# SensorBoard.net
KiCad netlist of a schematic drawn in Altium Designer
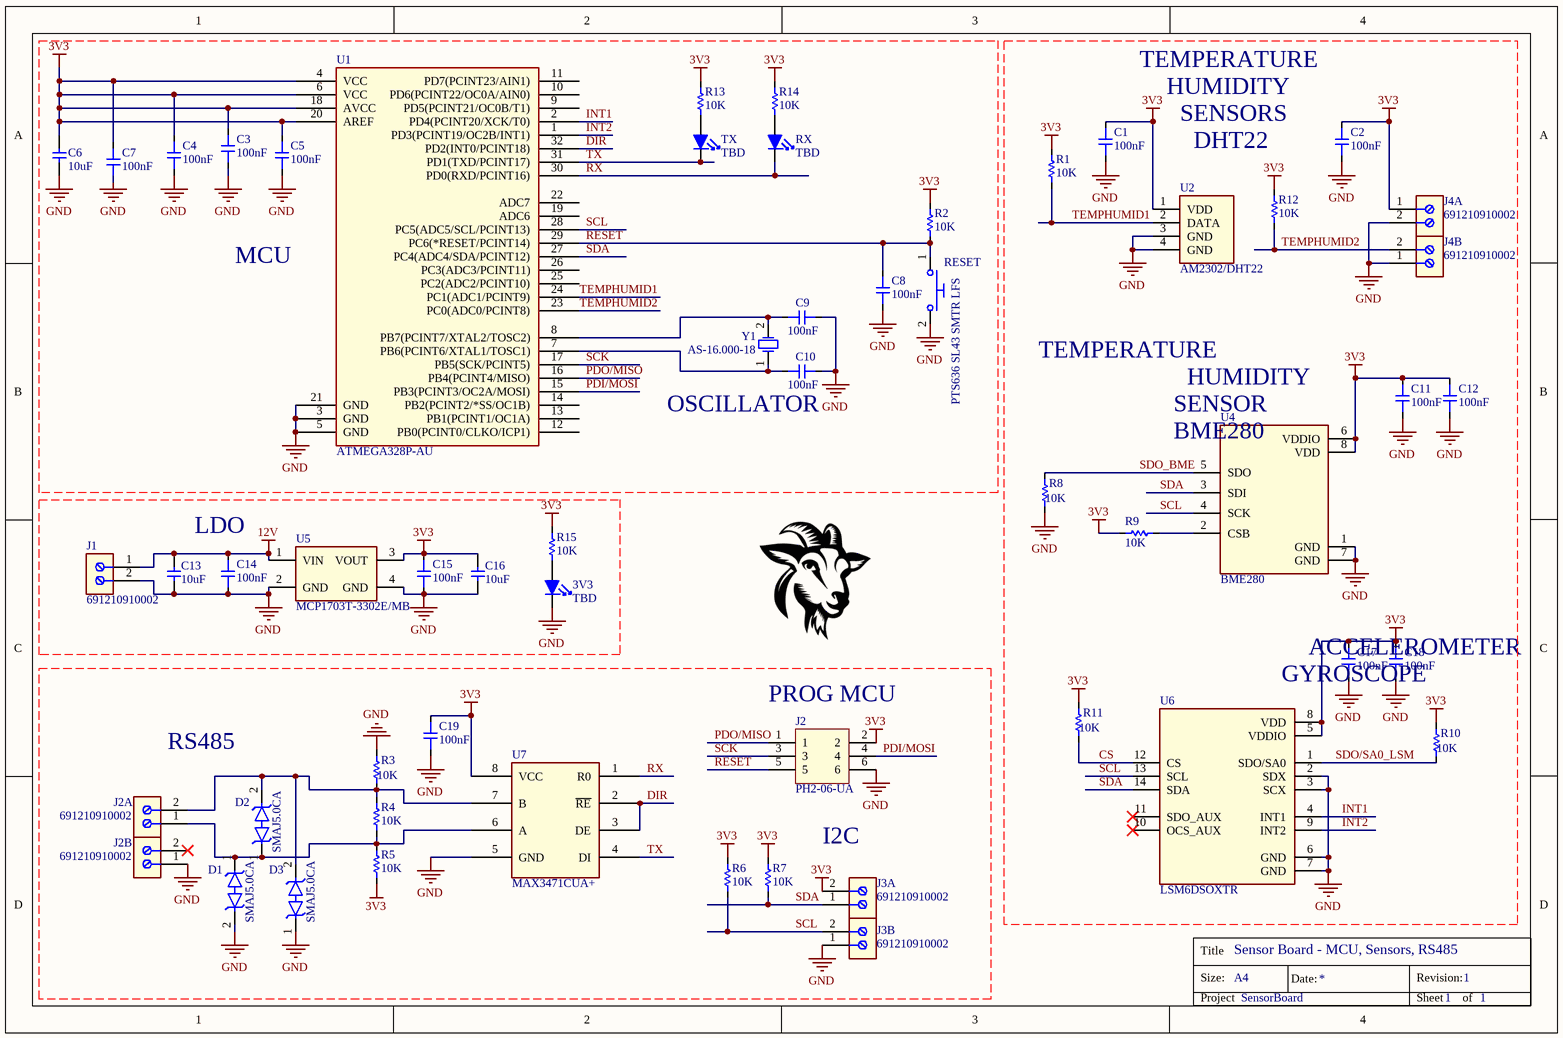
[diagram p0: SensorBoard.SchDoc]

(export (version "E")
  (design (tool "Eeschema 10.0.6"))
  (components
    (comp (ref "3V3")
      (value "TBD")
      (footprint "CASE0603")
      (description "Typical INFRARED GaAs LED")
      (libsource (lib "SensorBoard") (part "LED"))
    )
    (comp (ref "C1")
      (value "100nF")
      (footprint "CASE0603")
      (description "CAP CER 100nF 5% 25V X7R 0603")
      (fields (field (name "MFR") "KEMET"))
      (libsource (lib "SensorBoard") (part "Capacitor_100nF"))
    )
    (comp (ref "C2")
      (value "100nF")
      (footprint "CASE0603")
      (description "CAP CER 100nF 5% 25V X7R 0603")
      (fields (field (name "MFR") "KEMET"))
      (libsource (lib "SensorBoard") (part "Capacitor_100nF"))
    )
    (comp (ref "C3")
      (value "100nF")
      (footprint "CASE0603")
      (description "CAP CER 100nF 5% 25V X7R 0603")
      (fields (field (name "MFR") "KEMET"))
      (libsource (lib "SensorBoard") (part "Capacitor_100nF"))
    )
    (comp (ref "C4")
      (value "100nF")
      (footprint "CASE0603")
      (description "CAP CER 100nF 5% 25V X7R 0603")
      (fields (field (name "MFR") "KEMET"))
      (libsource (lib "SensorBoard") (part "Capacitor_100nF"))
    )
    (comp (ref "C5")
      (value "100nF")
      (footprint "CASE0603")
      (description "CAP CER 100nF 5% 25V X7R 0603")
      (fields (field (name "MFR") "KEMET"))
      (libsource (lib "SensorBoard") (part "Capacitor_100nF"))
    )
    (comp (ref "C6")
      (value "10uF")
      (footprint "CASE0603")
      (description "CAP CER 10uF 20% 25V X5R 0603")
      (fields (field (name "MFR") "TDK"))
      (libsource (lib "SensorBoard") (part "Capacitor_10uF"))
    )
    (comp (ref "C7")
      (value "100nF")
      (footprint "CASE0603")
      (description "CAP CER 100nF 5% 25V X7R 0603")
      (fields (field (name "MFR") "KEMET"))
      (libsource (lib "SensorBoard") (part "Capacitor_100nF"))
    )
    (comp (ref "C8")
      (value "100nF")
      (footprint "CASE0603")
      (description "CAP CER 100nF 5% 25V X7R 0603")
      (fields (field (name "MFR") "KEMET"))
      (libsource (lib "SensorBoard") (part "Capacitor_100nF"))
    )
    (comp (ref "C9")
      (value "100nF")
      (footprint "CASE0603")
      (description "CAP CER 100nF 5% 25V X7R 0603")
      (fields (field (name "MFR") "KEMET"))
      (libsource (lib "SensorBoard") (part "Capacitor_100nF"))
    )
    (comp (ref "C10")
      (value "100nF")
      (footprint "CASE0603")
      (description "CAP CER 100nF 5% 25V X7R 0603")
      (fields (field (name "MFR") "KEMET"))
      (libsource (lib "SensorBoard") (part "Capacitor_100nF"))
    )
    (comp (ref "C11")
      (value "100nF")
      (footprint "CASE0603")
      (description "CAP CER 100nF 5% 25V X7R 0603")
      (fields (field (name "MFR") "KEMET"))
      (libsource (lib "SensorBoard") (part "Capacitor_100nF"))
    )
    (comp (ref "C12")
      (value "100nF")
      (footprint "CASE0603")
      (description "CAP CER 100nF 5% 25V X7R 0603")
      (fields (field (name "MFR") "KEMET"))
      (libsource (lib "SensorBoard") (part "Capacitor_100nF"))
    )
    (comp (ref "C13")
      (value "10uF")
      (footprint "CASE0603")
      (description "CAP CER 10uF 20% 25V X5R 0603")
      (fields (field (name "MFR") "TDK"))
      (libsource (lib "SensorBoard") (part "Capacitor_10uF"))
    )
    (comp (ref "C14")
      (value "100nF")
      (footprint "CASE0603")
      (description "CAP CER 100nF 5% 25V X7R 0603")
      (fields (field (name "MFR") "KEMET"))
      (libsource (lib "SensorBoard") (part "Capacitor_100nF"))
    )
    (comp (ref "C15")
      (value "100nF")
      (footprint "CASE0603")
      (description "CAP CER 100nF 5% 25V X7R 0603")
      (fields (field (name "MFR") "KEMET"))
      (libsource (lib "SensorBoard") (part "Capacitor_100nF"))
    )
    (comp (ref "C16")
      (value "10uF")
      (footprint "CASE0603")
      (description "CAP CER 10uF 20% 25V X5R 0603")
      (fields (field (name "MFR") "TDK"))
      (libsource (lib "SensorBoard") (part "Capacitor_10uF"))
    )
    (comp (ref "C17")
      (value "100nF")
      (footprint "CASE0603")
      (description "CAP CER 100nF 5% 25V X7R 0603")
      (fields (field (name "MFR") "KEMET"))
      (libsource (lib "SensorBoard") (part "Capacitor_100nF"))
    )
    (comp (ref "C18")
      (value "100nF")
      (footprint "CASE0603")
      (description "CAP CER 100nF 5% 25V X7R 0603")
      (fields (field (name "MFR") "KEMET"))
      (libsource (lib "SensorBoard") (part "Capacitor_100nF"))
    )
    (comp (ref "C19")
      (value "100nF")
      (footprint "CASE0603")
      (description "CAP CER 100nF 5% 25V X7R 0603")
      (fields (field (name "MFR") "KEMET"))
      (libsource (lib "SensorBoard") (part "Capacitor_100nF"))
    )
    (comp (ref "D1")
      (value "SMAJ5.0CA")
      (footprint "SMA")
      (description "9.2V Clamp 43.5A Ipp Tvs Diode Surface Mount DO-214AC (SMA)")
      (fields (field (name "MFR") "Good-Ark Semiconductor"))
      (libsource (lib "SensorBoard") (part "Diode_SMAJ5.0CA"))
    )
    (comp (ref "D2")
      (value "SMAJ5.0CA")
      (footprint "SMA")
      (description "9.2V Clamp 43.5A Ipp Tvs Diode Surface Mount DO-214AC (SMA)")
      (fields (field (name "MFR") "Good-Ark Semiconductor"))
      (libsource (lib "SensorBoard") (part "Diode_SMAJ5.0CA"))
    )
    (comp (ref "D3")
      (value "SMAJ5.0CA")
      (footprint "SMA")
      (description "9.2V Clamp 43.5A Ipp Tvs Diode Surface Mount DO-214AC (SMA)")
      (fields (field (name "MFR") "Good-Ark Semiconductor"))
      (libsource (lib "SensorBoard") (part "Diode_SMAJ5.0CA"))
    )
    (comp (ref "J1")
      (value "691210910002")
      (footprint "691210910002")
      (description "TERM BLOCK 2P HORIZON 2.54MM PCB")
      (fields (field (name "MFR") "Wurth"))
      (libsource (lib "") (part "Connector_691210910002_3"))
    )
    (comp (ref "J2")
      (value "PH2-06-UA")
      (footprint "Header_2x3_2.54_Male")
      (description "Connector Header Through Hole 6 position 0.100\" (2.54mm)")
      (fields (field (name "MFR") "Adam Tech"))
      (libsource (lib "SensorBoard") (part "Connector_PH2-06-UA"))
    )
    (comp (ref "J2A")
      (value "691210910002")
      (footprint "691210910002")
      (description "TERM BLOCK 2P HORIZON 2.54MM PCB")
      (fields (field (name "MFR") "Wurth"))
      (libsource (lib "SensorBoard") (part "Connector_691210910002"))
    )
    (comp (ref "J2B")
      (value "691210910002")
      (footprint "691210910002")
      (description "TERM BLOCK 2P HORIZON 2.54MM PCB")
      (fields (field (name "MFR") "Wurth"))
      (libsource (lib "SensorBoard") (part "Connector_691210910002"))
    )
    (comp (ref "J3A")
      (value "691210910002")
      (footprint "691210910002")
      (description "TERM BLOCK 2P HORIZON 2.54MM PCB")
      (fields (field (name "MFR") "Wurth"))
      (libsource (lib "") (part "Connector_691210910002_1"))
    )
    (comp (ref "J3B")
      (value "691210910002")
      (footprint "691210910002")
      (description "TERM BLOCK 2P HORIZON 2.54MM PCB")
      (fields (field (name "MFR") "Wurth"))
      (libsource (lib "") (part "Connector_691210910002_1"))
    )
    (comp (ref "J4A")
      (value "691210910002")
      (footprint "691210910002")
      (description "TERM BLOCK 2P HORIZON 2.54MM PCB")
      (fields (field (name "MFR") "Wurth"))
      (libsource (lib "") (part "Connector_691210910002_2"))
    )
    (comp (ref "J4B")
      (value "691210910002")
      (footprint "691210910002")
      (description "TERM BLOCK 2P HORIZON 2.54MM PCB")
      (fields (field (name "MFR") "Wurth"))
      (libsource (lib "") (part "Connector_691210910002_1"))
    )
    (comp (ref "R1")
      (value "10K")
      (footprint "CASE0603")
      (description "RES 10K 1% 1/10W 0603")
      (fields (field (name "MFR") "YAGEO"))
      (libsource (lib "SensorBoard") (part "Resistor_10K_0603"))
    )
    (comp (ref "R2")
      (value "10K")
      (footprint "CASE0603")
      (description "RES 10K 1% 1/10W 0603")
      (fields (field (name "MFR") "YAGEO"))
      (libsource (lib "SensorBoard") (part "Resistor_10K_0603"))
    )
    (comp (ref "R3")
      (value "10K")
      (footprint "CASE0603")
      (description "RES 10K 1% 1/10W 0603")
      (fields (field (name "MFR") "YAGEO"))
      (libsource (lib "SensorBoard") (part "Resistor_10K_0603"))
    )
    (comp (ref "R4")
      (value "10K")
      (footprint "CASE0603")
      (description "RES 10K 1% 1/10W 0603")
      (fields (field (name "MFR") "YAGEO"))
      (libsource (lib "SensorBoard") (part "Resistor_10K_0603"))
    )
    (comp (ref "R5")
      (value "10K")
      (footprint "CASE0603")
      (description "RES 10K 1% 1/10W 0603")
      (fields (field (name "MFR") "YAGEO"))
      (libsource (lib "SensorBoard") (part "Resistor_10K_0603"))
    )
    (comp (ref "R6")
      (value "10K")
      (footprint "CASE0603")
      (description "RES 10K 1% 1/10W 0603")
      (fields (field (name "MFR") "YAGEO"))
      (libsource (lib "SensorBoard") (part "Resistor_10K_0603"))
    )
    (comp (ref "R7")
      (value "10K")
      (footprint "CASE0603")
      (description "RES 10K 1% 1/10W 0603")
      (fields (field (name "MFR") "YAGEO"))
      (libsource (lib "SensorBoard") (part "Resistor_10K_0603"))
    )
    (comp (ref "R8")
      (value "10K")
      (footprint "CASE0603")
      (description "RES 10K 1% 1/10W 0603")
      (fields (field (name "MFR") "YAGEO"))
      (libsource (lib "SensorBoard") (part "Resistor_10K_0603"))
    )
    (comp (ref "R9")
      (value "10K")
      (footprint "CASE0603")
      (description "RES 10K 1% 1/10W 0603")
      (fields (field (name "MFR") "YAGEO"))
      (libsource (lib "SensorBoard") (part "Resistor_10K_0603"))
    )
    (comp (ref "R10")
      (value "10K")
      (footprint "CASE0603")
      (description "RES 10K 1% 1/10W 0603")
      (fields (field (name "MFR") "YAGEO"))
      (libsource (lib "SensorBoard") (part "Resistor_10K_0603"))
    )
    (comp (ref "R11")
      (value "10K")
      (footprint "CASE0603")
      (description "RES 10K 1% 1/10W 0603")
      (fields (field (name "MFR") "YAGEO"))
      (libsource (lib "SensorBoard") (part "Resistor_10K_0603"))
    )
    (comp (ref "R12")
      (value "10K")
      (footprint "CASE0603")
      (description "RES 10K 1% 1/10W 0603")
      (fields (field (name "MFR") "YAGEO"))
      (libsource (lib "SensorBoard") (part "Resistor_10K_0603"))
    )
    (comp (ref "R13")
      (value "10K")
      (footprint "CASE0603")
      (description "RES 10K 1% 1/10W 0603")
      (fields (field (name "MFR") "YAGEO"))
      (libsource (lib "SensorBoard") (part "Resistor_10K_0603"))
    )
    (comp (ref "R14")
      (value "10K")
      (footprint "CASE0603")
      (description "RES 10K 1% 1/10W 0603")
      (fields (field (name "MFR") "YAGEO"))
      (libsource (lib "SensorBoard") (part "Resistor_10K_0603"))
    )
    (comp (ref "R15")
      (value "10K")
      (footprint "CASE0603")
      (description "RES 10K 1% 1/10W 0603")
      (fields (field (name "MFR") "YAGEO"))
      (libsource (lib "SensorBoard") (part "Resistor_10K_0603"))
    )
    (comp (ref "RESET")
      (value "PTS636 SL43 SMTR LFS")
      (footprint "SMT Button")
      (description "9.2V Clamp 43.5A Ipp Tvs Diode Surface Mount DO-214AC (SMA)")
      (fields (field (name "MFR") "C&K"))
      (libsource (lib "SensorBoard") (part "Button_PTS636 SL43 SMTR LFS"))
    )
    (comp (ref "RX")
      (value "TBD")
      (footprint "CASE0603")
      (description "Typical INFRARED GaAs LED")
      (libsource (lib "SensorBoard") (part "LED"))
    )
    (comp (ref "TX")
      (value "TBD")
      (footprint "CASE0603")
      (description "Typical INFRARED GaAs LED")
      (libsource (lib "SensorBoard") (part "LED"))
    )
    (comp (ref "U1")
      (value "ATMEGA328P-AU")
      (footprint "TQFP-32")
      (description "AVR AVR® ATmega Microcontroller IC 8-Bit 20MHz 32KB (16K x 16) FLASH 32-TQFP (7x7)")
      (libsource (lib "SensorBoard") (part "IC_ATMEGA328"))
    )
    (comp (ref "U2")
      (value "AM2302/DHT22")
      (footprint "AM2302_TEMP_HUMID_SENSOR")
      (description "DIGITAL HUMIDITY, PRESSURE AND TEMPERATURE SENSOR")
      (libsource (lib "SensorBoard") (part "IC_AM2302/DHT22"))
    )
    (comp (ref "U4")
      (value "BME280")
      (footprint "VFLGA-8")
      (description "DIGITAL HUMIDITY, PRESSURE AND TEMPERATURE SENSOR")
      (fields (field (name "MFR") "Bosch"))
      (libsource (lib "SensorBoard") (part "IC_BME280"))
    )
    (comp (ref "U5")
      (value "MCP1703T-3302E/MB")
      (footprint "SOT-223-3")
      (description "IC REG LINEAR 3.3V 250MA SOT89-3")
      (fields (field (name "MFR") "Microchip"))
      (libsource (lib "SensorBoard") (part "MCP1703T-3302E/MB"))
    )
    (comp (ref "U6")
      (value "LSM6DSOXTR")
      (footprint "VFLGA-14")
      (description "Accelerometer, Gyroscope, 6 Axis Sensor I²C, SPI Output")
      (fields (field (name "MFR") "STMicroelectronics"))
      (libsource (lib "SensorBoard") (part "IC_LSM6DSOXTR"))
    )
    (comp (ref "U7")
      (value "MAX3471CUA+")
      (footprint "TSSOP-8")
      (description "IC TRANSCEIVER HALF 1/1 8UMAX")
      (fields (field (name "MFR") "Analog Devices"))
      (libsource (lib "SensorBoard") (part "IC_MAX3471"))
    )
    (comp (ref "Y1")
      (value "AS-16.000-18")
      (footprint "HC-49/US")
      (description "16 MHz ±30ppm Crystal 18pF 40 Ohms HC-49/US")
      (fields (field (name "MFR") "Raltron Electronics"))
      (libsource (lib "SensorBoard") (part "Crystal_AS-16.000-18"))
    )
  )
  (nets
    (net (code "1") (name "/CS") (class "Default")
      (node (ref "R11") (pin "2") (pinfunction "2_2") (pintype "passive"))
      (node (ref "U6") (pin "12") (pinfunction "CS_12") (pintype "passive"))
    )
    (net (code "2") (name "/DIR") (class "Default")
      (node (ref "U1") (pin "32") (pinfunction "PD2(INT0/PCINT18)_32") (pintype "passive"))
      (node (ref "U7") (pin "2") (pinfunction "~{RE}_2") (pintype "passive"))
      (node (ref "U7") (pin "3") (pinfunction "DE_3") (pintype "passive"))
    )
    (net (code "3") (name "/INT1") (class "Default")
      (node (ref "U1") (pin "2") (pinfunction "PD4(PCINT20/XCK/T0)_2") (pintype "passive"))
      (node (ref "U6") (pin "4") (pinfunction "INT1_4") (pintype "passive"))
    )
    (net (code "4") (name "/INT2") (class "Default")
      (node (ref "U1") (pin "1") (pinfunction "PD3(PCINT19/OC2B/INT1)_1") (pintype "passive"))
      (node (ref "U6") (pin "9") (pinfunction "INT2_9") (pintype "passive"))
    )
    (net (code "5") (name "/PDI{slash}MOSI") (class "Default")
      (node (ref "J2") (pin "4") (pinfunction "4_4") (pintype "passive"))
      (node (ref "U1") (pin "15") (pinfunction "PB3(PCINT3/OC2A/MOSI)_15") (pintype "passive"))
    )
    (net (code "6") (name "/PDO{slash}MISO") (class "Default")
      (node (ref "J2") (pin "1") (pinfunction "1_1") (pintype "passive"))
      (node (ref "U1") (pin "16") (pinfunction "PB4(PCINT4/MISO)_16") (pintype "passive"))
    )
    (net (code "7") (name "/RX") (class "Default")
      (node (ref "RX") (pin "2") (pinfunction "K_2") (pintype "passive"))
      (node (ref "U1") (pin "30") (pinfunction "PD0(RXD/PCINT16)_30") (pintype "passive"))
      (node (ref "U7") (pin "1") (pinfunction "R0_1") (pintype "passive"))
    )
    (net (code "8") (name "/SCK") (class "Default")
      (node (ref "J2") (pin "3") (pinfunction "3_3") (pintype "passive"))
      (node (ref "U1") (pin "17") (pinfunction "PB5(SCK/PCINT5)_17") (pintype "passive"))
    )
    (net (code "9") (name "/SCL") (class "Default")
      (node (ref "J3B") (pin "2") (pinfunction "2_2") (pintype "passive"))
      (node (ref "R6") (pin "2") (pinfunction "2_2") (pintype "passive"))
      (node (ref "U1") (pin "28") (pinfunction "PC5(ADC5/SCL/PCINT13)_28") (pintype "passive"))
      (node (ref "U4") (pin "4") (pinfunction "SCK_4") (pintype "passive"))
      (node (ref "U6") (pin "13") (pinfunction "SCL_13") (pintype "passive"))
    )
    (net (code "10") (name "/SDA") (class "Default")
      (node (ref "J3A") (pin "1") (pinfunction "1_1") (pintype "passive"))
      (node (ref "R7") (pin "2") (pinfunction "2_2") (pintype "passive"))
      (node (ref "U1") (pin "27") (pinfunction "PC4(ADC4/SDA/PCINT12)_27") (pintype "passive"))
      (node (ref "U4") (pin "3") (pinfunction "SDI_3") (pintype "passive"))
      (node (ref "U6") (pin "14") (pinfunction "SDA_14") (pintype "passive"))
    )
    (net (code "11") (name "/SDO_BME") (class "Default")
      (node (ref "R8") (pin "1") (pinfunction "1_1") (pintype "passive"))
      (node (ref "U4") (pin "5") (pinfunction "SDO_5") (pintype "passive"))
    )
    (net (code "12") (name "/SDO{slash}SA0_LSM") (class "Default")
      (node (ref "R10") (pin "2") (pinfunction "2_2") (pintype "passive"))
      (node (ref "U6") (pin "1") (pinfunction "SDO/SA0_1") (pintype "passive"))
    )
    (net (code "13") (name "/TEMPHUMID1") (class "Default")
      (node (ref "R1") (pin "2") (pinfunction "2_2") (pintype "passive"))
      (node (ref "U1") (pin "24") (pinfunction "PC1(ADC1/PCINT9)_24") (pintype "passive"))
      (node (ref "U2") (pin "2") (pinfunction "DATA_2") (pintype "power_in"))
    )
    (net (code "14") (name "/TEMPHUMID2") (class "Default")
      (node (ref "J4B") (pin "2") (pinfunction "2_2") (pintype "passive"))
      (node (ref "R12") (pin "2") (pinfunction "2_2") (pintype "passive"))
      (node (ref "U1") (pin "23") (pinfunction "PC0(ADC0/PCINT8)_23") (pintype "passive"))
    )
    (net (code "15") (name "/TX") (class "Default")
      (node (ref "TX") (pin "2") (pinfunction "K_2") (pintype "passive"))
      (node (ref "U1") (pin "31") (pinfunction "PD1(TXD/PCINT17)_31") (pintype "passive"))
      (node (ref "U7") (pin "4") (pinfunction "DI_4") (pintype "passive"))
    )
    (net (code "16") (name "/~{RESET}") (class "Default")
      (node (ref "C8") (pin "1") (pinfunction "1_1") (pintype "passive"))
      (node (ref "J2") (pin "5") (pinfunction "5_5") (pintype "passive"))
      (node (ref "R2") (pin "2") (pinfunction "2_2") (pintype "passive"))
      (node (ref "RESET") (pin "1") (pinfunction "1_1") (pintype "passive"))
      (node (ref "U1") (pin "29") (pinfunction "PC6(*RESET/PCINT14)_29") (pintype "passive"))
    )
    (net (code "17") (name "3V3") (class "Default")
      (node (ref "C1") (pin "1") (pinfunction "1_1") (pintype "passive"))
      (node (ref "C11") (pin "1") (pinfunction "1_1") (pintype "passive"))
      (node (ref "C12") (pin "1") (pinfunction "1_1") (pintype "passive"))
      (node (ref "C15") (pin "2") (pinfunction "2_2") (pintype "passive"))
      (node (ref "C16") (pin "2") (pinfunction "2_2") (pintype "passive"))
      (node (ref "C17") (pin "1") (pinfunction "1_1") (pintype "passive"))
      (node (ref "C18") (pin "1") (pinfunction "1_1") (pintype "passive"))
      (node (ref "C19") (pin "2") (pinfunction "2_2") (pintype "passive"))
      (node (ref "C2") (pin "1") (pinfunction "1_1") (pintype "passive"))
      (node (ref "C3") (pin "2") (pinfunction "2_2") (pintype "passive"))
      (node (ref "C4") (pin "2") (pinfunction "2_2") (pintype "passive"))
      (node (ref "C5") (pin "2") (pinfunction "2_2") (pintype "passive"))
      (node (ref "C6") (pin "2") (pinfunction "2_2") (pintype "passive"))
      (node (ref "C7") (pin "2") (pinfunction "2_2") (pintype "passive"))
      (node (ref "J2") (pin "2") (pinfunction "2_2") (pintype "passive"))
      (node (ref "J3A") (pin "2") (pinfunction "2_2") (pintype "passive"))
      (node (ref "J4A") (pin "1") (pinfunction "1_1") (pintype "passive"))
      (node (ref "R1") (pin "1") (pinfunction "1_1") (pintype "passive"))
      (node (ref "R10") (pin "1") (pinfunction "1_1") (pintype "passive"))
      (node (ref "R11") (pin "1") (pinfunction "1_1") (pintype "passive"))
      (node (ref "R12") (pin "1") (pinfunction "1_1") (pintype "passive"))
      (node (ref "R13") (pin "1") (pinfunction "1_1") (pintype "passive"))
      (node (ref "R14") (pin "1") (pinfunction "1_1") (pintype "passive"))
      (node (ref "R15") (pin "1") (pinfunction "1_1") (pintype "passive"))
      (node (ref "R2") (pin "1") (pinfunction "1_1") (pintype "passive"))
      (node (ref "R5") (pin "2") (pinfunction "2_2") (pintype "passive"))
      (node (ref "R6") (pin "1") (pinfunction "1_1") (pintype "passive"))
      (node (ref "R7") (pin "1") (pinfunction "1_1") (pintype "passive"))
      (node (ref "R9") (pin "1") (pinfunction "1_1") (pintype "passive"))
      (node (ref "U1") (pin "18") (pinfunction "AVCC_18") (pintype "passive"))
      (node (ref "U1") (pin "20") (pinfunction "AREF_20") (pintype "passive"))
      (node (ref "U1") (pin "4") (pinfunction "VCC_4") (pintype "passive"))
      (node (ref "U1") (pin "6") (pinfunction "VCC_6") (pintype "passive"))
      (node (ref "U2") (pin "1") (pinfunction "VDD_1") (pintype "power_in"))
      (node (ref "U4") (pin "6") (pinfunction "VDDIO_6") (pintype "power_in"))
      (node (ref "U4") (pin "8") (pinfunction "VDD_8") (pintype "power_in"))
      (node (ref "U5") (pin "3") (pinfunction "VOUT_3") (pintype "passive"))
      (node (ref "U6") (pin "5") (pinfunction "VDDIO_5") (pintype "passive"))
      (node (ref "U6") (pin "8") (pinfunction "VDD_8") (pintype "passive"))
      (node (ref "U7") (pin "8") (pinfunction "VCC_8") (pintype "passive"))
    )
    (net (code "18") (name "12V") (class "Default")
      (node (ref "C13") (pin "2") (pinfunction "2_2") (pintype "passive"))
      (node (ref "C14") (pin "2") (pinfunction "2_2") (pintype "passive"))
      (node (ref "J1") (pin "1") (pinfunction "1_1") (pintype "passive"))
      (node (ref "U5") (pin "1") (pinfunction "VIN_1") (pintype "passive"))
    )
    (net (code "19") (name "GND") (class "Default")
      (node (ref "3V3") (pin "2") (pinfunction "K_2") (pintype "passive"))
      (node (ref "C1") (pin "2") (pinfunction "2_2") (pintype "passive"))
      (node (ref "C10") (pin "1") (pinfunction "1_1") (pintype "passive"))
      (node (ref "C11") (pin "2") (pinfunction "2_2") (pintype "passive"))
      (node (ref "C12") (pin "2") (pinfunction "2_2") (pintype "passive"))
      (node (ref "C13") (pin "1") (pinfunction "1_1") (pintype "passive"))
      (node (ref "C14") (pin "1") (pinfunction "1_1") (pintype "passive"))
      (node (ref "C15") (pin "1") (pinfunction "1_1") (pintype "passive"))
      (node (ref "C16") (pin "1") (pinfunction "1_1") (pintype "passive"))
      (node (ref "C17") (pin "2") (pinfunction "2_2") (pintype "passive"))
      (node (ref "C18") (pin "2") (pinfunction "2_2") (pintype "passive"))
      (node (ref "C19") (pin "1") (pinfunction "1_1") (pintype "passive"))
      (node (ref "C2") (pin "2") (pinfunction "2_2") (pintype "passive"))
      (node (ref "C3") (pin "1") (pinfunction "1_1") (pintype "passive"))
      (node (ref "C4") (pin "1") (pinfunction "1_1") (pintype "passive"))
      (node (ref "C5") (pin "1") (pinfunction "1_1") (pintype "passive"))
      (node (ref "C6") (pin "1") (pinfunction "1_1") (pintype "passive"))
      (node (ref "C7") (pin "1") (pinfunction "1_1") (pintype "passive"))
      (node (ref "C8") (pin "2") (pinfunction "2_2") (pintype "passive"))
      (node (ref "C9") (pin "1") (pinfunction "1_1") (pintype "passive"))
      (node (ref "D1") (pin "2") (pinfunction "2_2") (pintype "passive"))
      (node (ref "D3") (pin "1") (pinfunction "1_1") (pintype "passive"))
      (node (ref "J1") (pin "2") (pinfunction "2_2") (pintype "passive"))
      (node (ref "J2") (pin "6") (pinfunction "6_6") (pintype "passive"))
      (node (ref "J2B") (pin "1") (pinfunction "1_1") (pintype "passive"))
      (node (ref "J3B") (pin "1") (pinfunction "1_1") (pintype "passive"))
      (node (ref "J4A") (pin "2") (pinfunction "2_2") (pintype "passive"))
      (node (ref "J4B") (pin "1") (pinfunction "1_1") (pintype "passive"))
      (node (ref "R3") (pin "1") (pinfunction "1_1") (pintype "passive"))
      (node (ref "R8") (pin "2") (pinfunction "2_2") (pintype "passive"))
      (node (ref "RESET") (pin "2") (pinfunction "2_2") (pintype "passive"))
      (node (ref "U1") (pin "21") (pinfunction "GND_21") (pintype "passive"))
      (node (ref "U1") (pin "3") (pinfunction "GND_3") (pintype "passive"))
      (node (ref "U1") (pin "5") (pinfunction "GND_5") (pintype "passive"))
      (node (ref "U2") (pin "3") (pinfunction "GND_3") (pintype "power_in"))
      (node (ref "U2") (pin "4") (pinfunction "GND_4") (pintype "power_in"))
      (node (ref "U4") (pin "1") (pinfunction "GND_1") (pintype "power_in"))
      (node (ref "U4") (pin "7") (pinfunction "GND_7") (pintype "power_in"))
      (node (ref "U5") (pin "2") (pinfunction "GND_2") (pintype "passive"))
      (node (ref "U5") (pin "4") (pinfunction "GND_4") (pintype "passive"))
      (node (ref "U6") (pin "2") (pinfunction "SDX_2") (pintype "passive"))
      (node (ref "U6") (pin "3") (pinfunction "SCX_3") (pintype "passive"))
      (node (ref "U6") (pin "6") (pinfunction "GND_6") (pintype "passive"))
      (node (ref "U6") (pin "7") (pinfunction "GND_7") (pintype "passive"))
      (node (ref "U7") (pin "5") (pinfunction "GND_5") (pintype "passive"))
    )
    (net (code "20") (name "Net-(3V3-A)") (class "Default")
      (node (ref "3V3") (pin "1") (pinfunction "A_1") (pintype "passive"))
      (node (ref "R15") (pin "2") (pinfunction "2_2") (pintype "passive"))
    )
    (net (code "21") (name "Net-(RX-A)") (class "Default")
      (node (ref "R14") (pin "2") (pinfunction "2_2") (pintype "passive"))
      (node (ref "RX") (pin "1") (pinfunction "A_1") (pintype "passive"))
    )
    (net (code "22") (name "Net-(TX-A)") (class "Default")
      (node (ref "R13") (pin "2") (pinfunction "2_2") (pintype "passive"))
      (node (ref "TX") (pin "1") (pinfunction "A_1") (pintype "passive"))
    )
    (net (code "23") (name "Net-(U1-PB6(PCINT6{slash}XTAL1{slash}TOSC1))") (class "Default")
      (node (ref "C10") (pin "2") (pinfunction "2_2") (pintype "passive"))
      (node (ref "U1") (pin "7") (pinfunction "PB6(PCINT6/XTAL1/TOSC1)_7") (pintype "passive"))
      (node (ref "Y1") (pin "1") (pinfunction "OSC1_1") (pintype "passive"))
    )
    (net (code "24") (name "Net-(U1-PB7(PCINT7{slash}XTAL2{slash}TOSC2))") (class "Default")
      (node (ref "C9") (pin "2") (pinfunction "2_2") (pintype "passive"))
      (node (ref "U1") (pin "8") (pinfunction "PB7(PCINT7/XTAL2/TOSC2)_8") (pintype "passive"))
      (node (ref "Y1") (pin "2") (pinfunction "OSC2_2") (pintype "passive"))
    )
    (net (code "25") (name "Net-(U4-CSB)") (class "Default")
      (node (ref "R9") (pin "2") (pinfunction "2_2") (pintype "passive"))
      (node (ref "U4") (pin "2") (pinfunction "CSB_2") (pintype "passive"))
    )
    (net (code "26") (name "Net-(U7-A)") (class "Default")
      (node (ref "D1") (pin "1") (pinfunction "1_1") (pintype "passive"))
      (node (ref "D2") (pin "1") (pinfunction "1_1") (pintype "passive"))
      (node (ref "J2A") (pin "1") (pinfunction "1_1") (pintype "passive"))
      (node (ref "R4") (pin "2") (pinfunction "2_2") (pintype "passive"))
      (node (ref "R5") (pin "1") (pinfunction "1_1") (pintype "passive"))
      (node (ref "U7") (pin "6") (pinfunction "A_6") (pintype "passive"))
    )
    (net (code "27") (name "Net-(U7-B)") (class "Default")
      (node (ref "D2") (pin "2") (pinfunction "2_2") (pintype "passive"))
      (node (ref "D3") (pin "2") (pinfunction "2_2") (pintype "passive"))
      (node (ref "J2A") (pin "2") (pinfunction "2_2") (pintype "passive"))
      (node (ref "R3") (pin "2") (pinfunction "2_2") (pintype "passive"))
      (node (ref "R4") (pin "1") (pinfunction "1_1") (pintype "passive"))
      (node (ref "U7") (pin "7") (pinfunction "B_7") (pintype "passive"))
    )
    (net (code "28") (name "unconnected-(J2B-Pad2)") (class "Default")
      (node (ref "J2B") (pin "2") (pinfunction "2_2") (pintype "passive+no_connect"))
    )
    (net (code "29") (name "unconnected-(U1-ADC6-Pad19)") (class "Default")
      (node (ref "U1") (pin "19") (pinfunction "ADC6_19") (pintype "passive"))
    )
    (net (code "30") (name "unconnected-(U1-ADC7-Pad22)") (class "Default")
      (node (ref "U1") (pin "22") (pinfunction "ADC7_22") (pintype "passive"))
    )
    (net (code "31") (name "unconnected-(U1-PB0(PCINT0{slash}CLKO{slash}ICP1)-Pad12)") (class "Default")
      (node (ref "U1") (pin "12") (pinfunction "PB0(PCINT0/CLKO/ICP1)_12") (pintype "passive"))
    )
    (net (code "32") (name "unconnected-(U1-PB1(PCINT1{slash}OC1A)-Pad13)") (class "Default")
      (node (ref "U1") (pin "13") (pinfunction "PB1(PCINT1/OC1A)_13") (pintype "passive"))
    )
    (net (code "33") (name "unconnected-(U1-PB2(PCINT2{slash}*SS{slash}OC1B)-Pad14)") (class "Default")
      (node (ref "U1") (pin "14") (pinfunction "PB2(PCINT2/*SS/OC1B)_14") (pintype "passive"))
    )
    (net (code "34") (name "unconnected-(U1-PC2(ADC2{slash}PCINT10)-Pad25)") (class "Default")
      (node (ref "U1") (pin "25") (pinfunction "PC2(ADC2/PCINT10)_25") (pintype "passive"))
    )
    (net (code "35") (name "unconnected-(U1-PC3(ADC3{slash}PCINT11)-Pad26)") (class "Default")
      (node (ref "U1") (pin "26") (pinfunction "PC3(ADC3/PCINT11)_26") (pintype "passive"))
    )
    (net (code "36") (name "unconnected-(U1-PD5(PCINT21{slash}OC0B{slash}T1)-Pad9)") (class "Default")
      (node (ref "U1") (pin "9") (pinfunction "PD5(PCINT21/OC0B/T1)_9") (pintype "passive"))
    )
    (net (code "37") (name "unconnected-(U1-PD6(PCINT22{slash}OC0A{slash}AIN0)-Pad10)") (class "Default")
      (node (ref "U1") (pin "10") (pinfunction "PD6(PCINT22/OC0A/AIN0)_10") (pintype "passive"))
    )
    (net (code "38") (name "unconnected-(U1-PD7(PCINT23{slash}AIN1)-Pad11)") (class "Default")
      (node (ref "U1") (pin "11") (pinfunction "PD7(PCINT23/AIN1)_11") (pintype "passive"))
    )
    (net (code "39") (name "unconnected-(U6-OCS_AUX-Pad10)") (class "Default")
      (node (ref "U6") (pin "10") (pinfunction "OCS_AUX_10") (pintype "passive+no_connect"))
    )
    (net (code "40") (name "unconnected-(U6-SDO_AUX-Pad11)") (class "Default")
      (node (ref "U6") (pin "11") (pinfunction "SDO_AUX_11") (pintype "passive+no_connect"))
    )
  )
)
